# schematic-breadboard.net
KiCad netlist of a schematic drawn in EAGLE
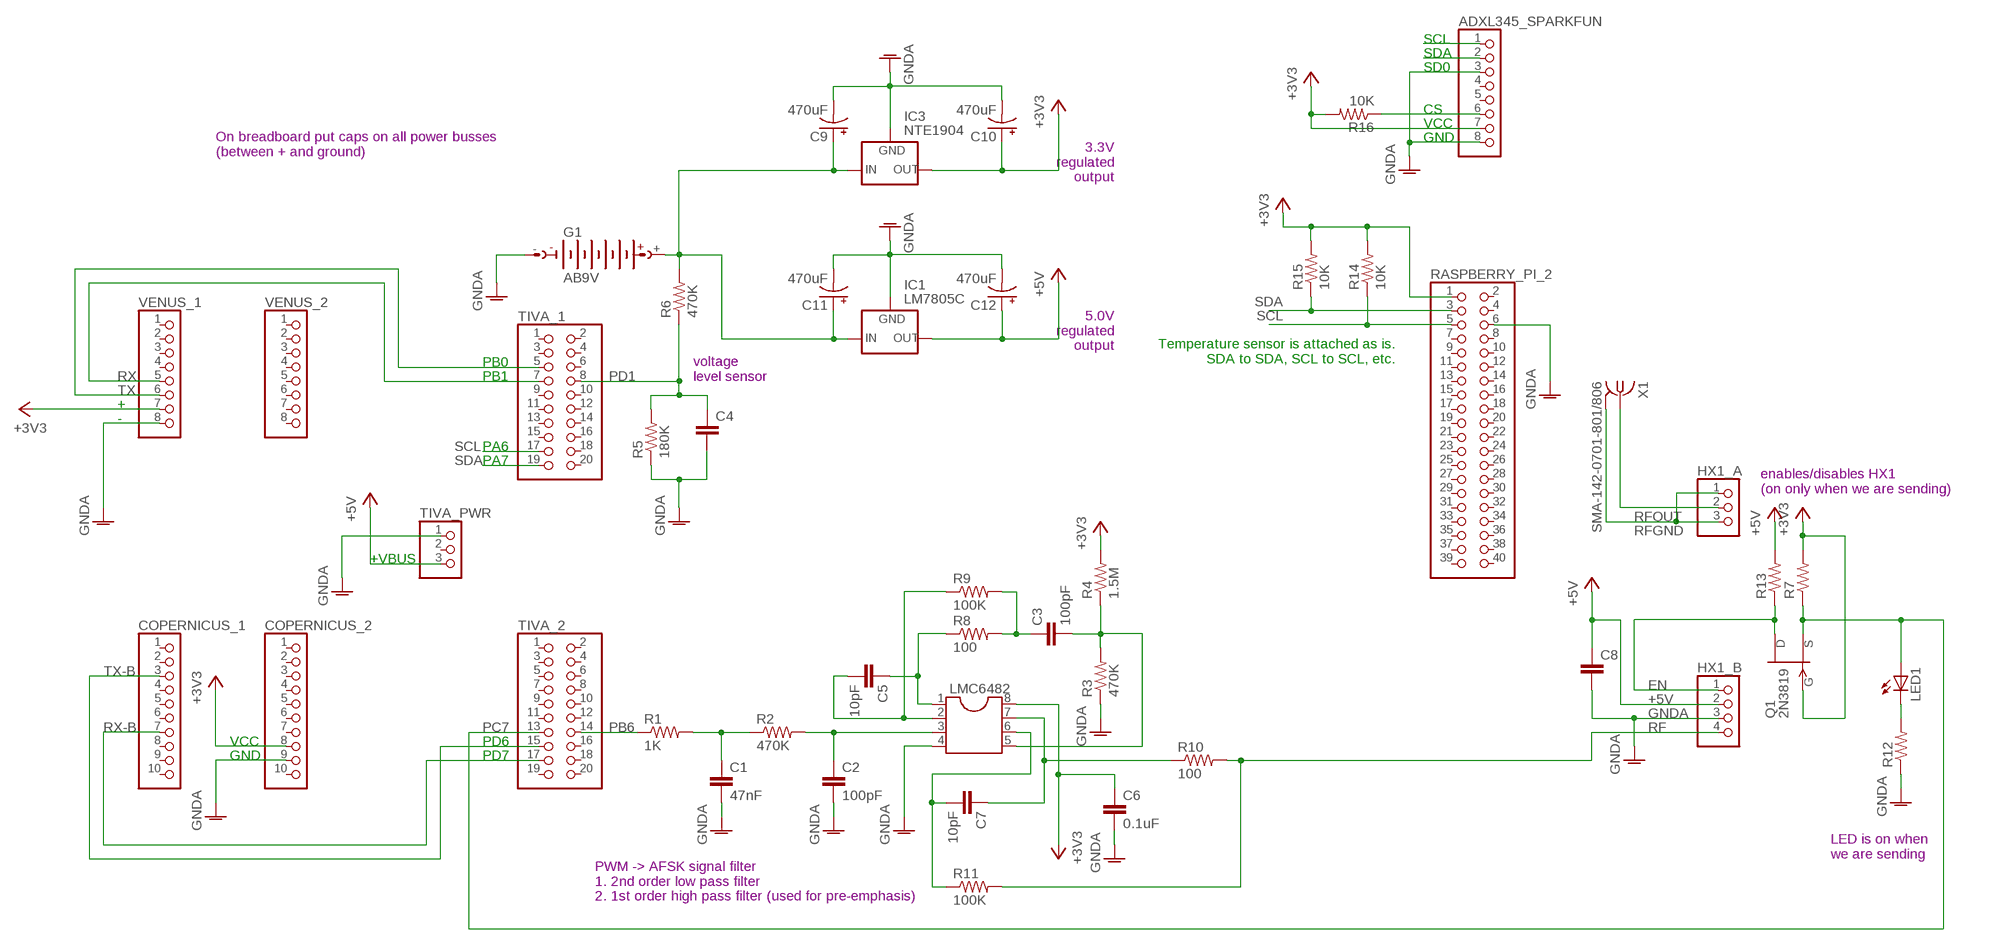
[diagram p0: schematic, sheet 1]

(export (version "E")
  (design (tool "Eeschema 10.0.6"))
  (components
    (comp (ref "ADXL345_SPARKFUN")
      (value "PINHD-1X8")
      (footprint "eagle-import:1X08")
      (libsource (lib "eagle-import") (part "PINHD-1X8"))
    )
    (comp (ref "C1")
      (value "47nF")
      (footprint "eagle-import:C2.5-2")
      (libsource (lib "eagle-import") (part "C2.5/2"))
    )
    (comp (ref "C2")
      (value "100pF")
      (footprint "eagle-import:C2.5-2")
      (libsource (lib "eagle-import") (part "C2.5/2"))
    )
    (comp (ref "C3")
      (value "100pF")
      (footprint "eagle-import:C2.5-2")
      (libsource (lib "eagle-import") (part "C2.5/2"))
    )
    (comp (ref "C4")
      (value "C2.5/2")
      (footprint "eagle-import:C2.5-2")
      (libsource (lib "eagle-import") (part "C2.5/2"))
    )
    (comp (ref "C5")
      (value "10pF")
      (footprint "eagle-import:C2.5-2")
      (libsource (lib "eagle-import") (part "C2.5/2"))
    )
    (comp (ref "C6")
      (value "0.1uF")
      (footprint "eagle-import:C2.5-2")
      (libsource (lib "eagle-import") (part "C2.5/2"))
    )
    (comp (ref "C7")
      (value "10pF")
      (footprint "eagle-import:C2.5-2")
      (libsource (lib "eagle-import") (part "C2.5/2"))
    )
    (comp (ref "C8")
      (value "C2.5/2")
      (footprint "eagle-import:C2.5-2")
      (libsource (lib "eagle-import") (part "C2.5/2"))
    )
    (comp (ref "C9")
      (value "470uF")
      (footprint "eagle-import:E2,5-6E")
      (libsource (lib "eagle-import") (part "CPOL-USE2,5-6E"))
    )
    (comp (ref "C10")
      (value "470uF")
      (footprint "eagle-import:E2,5-6E")
      (libsource (lib "eagle-import") (part "CPOL-USE2,5-6E"))
    )
    (comp (ref "C11")
      (value "470uF")
      (footprint "eagle-import:E2,5-6E")
      (libsource (lib "eagle-import") (part "CPOL-USE2,5-6E"))
    )
    (comp (ref "C12")
      (value "470uF")
      (footprint "eagle-import:E2,5-6E")
      (libsource (lib "eagle-import") (part "CPOL-USE2,5-6E"))
    )
    (comp (ref "COPERNICUS_1")
      (value "PINHD-1X10")
      (footprint "eagle-import:1X10")
      (libsource (lib "eagle-import") (part "PINHD-1X10"))
    )
    (comp (ref "COPERNICUS_2")
      (value "PINHD-1X10")
      (footprint "eagle-import:1X10")
      (libsource (lib "eagle-import") (part "PINHD-1X10"))
    )
    (comp (ref "G1")
      (value "AB9V")
      (footprint "eagle-import:AB9V")
      (libsource (lib "eagle-import") (part "AB9V"))
    )
    (comp (ref "HX1_A")
      (value "PINHD-1X3")
      (footprint "eagle-import:1X03")
      (libsource (lib "eagle-import") (part "PINHD-1X3"))
    )
    (comp (ref "HX1_B")
      (value "PINHD-1X4")
      (footprint "eagle-import:1X04")
      (libsource (lib "eagle-import") (part "PINHD-1X4"))
    )
    (comp (ref "IC1")
      (value "LM7805C")
      (footprint "eagle-import:79XXL")
      (libsource (lib "eagle-import") (part "79XXL"))
    )
    (comp (ref "IC3")
      (value "NTE1904")
      (footprint "eagle-import:79XXL")
      (libsource (lib "eagle-import") (part "79XXL"))
    )
    (comp (ref "LED1")
      (value "LED3MM")
      (footprint "eagle-import:LED3MM")
      (libsource (lib "eagle-import") (part "LED3MM"))
    )
    (comp (ref "LMC6482")
      (value "DIL8")
      (footprint "eagle-import:DIL08")
      (libsource (lib "eagle-import") (part "DIL8"))
    )
    (comp (ref "Q1")
      (value "2N3819")
      (footprint "eagle-import:TO92")
      (libsource (lib "eagle-import") (part "2N3819"))
    )
    (comp (ref "R1")
      (value "1K")
      (footprint "eagle-import:0204V")
      (libsource (lib "eagle-import") (part "R-US_0204/2V"))
    )
    (comp (ref "R2")
      (value "470K")
      (footprint "eagle-import:0204V")
      (libsource (lib "eagle-import") (part "R-US_0204/2V"))
    )
    (comp (ref "R3")
      (value "470K")
      (footprint "eagle-import:0204V")
      (libsource (lib "eagle-import") (part "R-US_0204/2V"))
    )
    (comp (ref "R4")
      (value "1.5M")
      (footprint "eagle-import:0204V")
      (libsource (lib "eagle-import") (part "R-US_0204/2V"))
    )
    (comp (ref "R5")
      (value "180K")
      (footprint "eagle-import:0204V")
      (libsource (lib "eagle-import") (part "R-US_0204/2V"))
    )
    (comp (ref "R6")
      (value "470K")
      (footprint "eagle-import:0204V")
      (libsource (lib "eagle-import") (part "R-US_0204/2V"))
    )
    (comp (ref "R7")
      (value "R-US_0204/2V")
      (footprint "eagle-import:0204V")
      (libsource (lib "eagle-import") (part "R-US_0204/2V"))
    )
    (comp (ref "R8")
      (value "100")
      (footprint "eagle-import:0204V")
      (libsource (lib "eagle-import") (part "R-US_0204/2V"))
    )
    (comp (ref "R9")
      (value "100K")
      (footprint "eagle-import:0204V")
      (libsource (lib "eagle-import") (part "R-US_0204/2V"))
    )
    (comp (ref "R10")
      (value "100")
      (footprint "eagle-import:0204V")
      (libsource (lib "eagle-import") (part "R-US_0204/2V"))
    )
    (comp (ref "R11")
      (value "100K")
      (footprint "eagle-import:0204V")
      (libsource (lib "eagle-import") (part "R-US_0204/2V"))
    )
    (comp (ref "R12")
      (value "R-US_0204/2V")
      (footprint "eagle-import:0204V")
      (libsource (lib "eagle-import") (part "R-US_0204/2V"))
    )
    (comp (ref "R13")
      (value "R-US_0204/2V")
      (footprint "eagle-import:0204V")
      (libsource (lib "eagle-import") (part "R-US_0204/2V"))
    )
    (comp (ref "R14")
      (value "10K")
      (footprint "eagle-import:0204V")
      (libsource (lib "eagle-import") (part "R-US_0204/2V"))
    )
    (comp (ref "R15")
      (value "10K")
      (footprint "eagle-import:0204V")
      (libsource (lib "eagle-import") (part "R-US_0204/2V"))
    )
    (comp (ref "R16")
      (value "10K")
      (footprint "eagle-import:0204V")
      (libsource (lib "eagle-import") (part "R-US_0204/2V"))
    )
    (comp (ref "RASPBERRY_PI_2")
      (value "PINHD-2X20")
      (footprint "eagle-import:2X20")
      (libsource (lib "eagle-import") (part "PINHD-2X20"))
    )
    (comp (ref "TIVA_1")
      (value "PINHD-2X10")
      (footprint "eagle-import:2X10")
      (libsource (lib "eagle-import") (part "PINHD-2X10"))
    )
    (comp (ref "TIVA_2")
      (value "PINHD-2X10")
      (footprint "eagle-import:2X10")
      (libsource (lib "eagle-import") (part "PINHD-2X10"))
    )
    (comp (ref "TIVA_PWR")
      (value "PINHD-1X3")
      (footprint "eagle-import:1X03")
      (libsource (lib "eagle-import") (part "PINHD-1X3"))
    )
    (comp (ref "VENUS_1")
      (value "PINHD-1X8")
      (footprint "eagle-import:1X08")
      (libsource (lib "eagle-import") (part "PINHD-1X8"))
    )
    (comp (ref "VENUS_2")
      (value "PINHD-1X8")
      (footprint "eagle-import:1X08")
      (libsource (lib "eagle-import") (part "PINHD-1X8"))
    )
    (comp (ref "X1")
      (value "SMA-142-0701-801/806")
      (footprint "eagle-import:J502-ND-142-0701-801_806")
      (fields (field (name "MF") "JOHNSON COMPONENTS") (field (name "MPN") "142-0701-801"))
      (libsource (lib "eagle-import") (part "SMA-142-0701-801/806"))
    )
  )
  (nets
    (net (code "1") (name "+3V3") (class "Default")
      (node (ref "ADXL345_SPARKFUN") (pin "7") (pinfunction "7_7") (pintype "passive"))
      (node (ref "C10") (pin "+") (pinfunction "+_+") (pintype "passive"))
      (node (ref "C6") (pin "1") (pinfunction "1_1") (pintype "passive"))
      (node (ref "COPERNICUS_2") (pin "8") (pinfunction "8_8") (pintype "passive"))
      (node (ref "IC3") (pin "OUT") (pinfunction "OUT_OUT") (pintype "passive"))
      (node (ref "LMC6482") (pin "8") (pinfunction "8_8") (pintype "passive"))
      (node (ref "Q1") (pin "2") (pinfunction "G_2") (pintype "passive"))
      (node (ref "R14") (pin "2") (pinfunction "2_2") (pintype "passive"))
      (node (ref "R15") (pin "2") (pinfunction "2_2") (pintype "passive"))
      (node (ref "R16") (pin "2") (pinfunction "2_2") (pintype "passive"))
      (node (ref "R4") (pin "2") (pinfunction "2_2") (pintype "passive"))
      (node (ref "R7") (pin "2") (pinfunction "2_2") (pintype "passive"))
      (node (ref "RASPBERRY_PI_2") (pin "1") (pinfunction "1_1") (pintype "passive"))
      (node (ref "VENUS_1") (pin "7") (pinfunction "7_7") (pintype "passive"))
    )
    (net (code "2") (name "+5V") (class "Default")
      (node (ref "C12") (pin "+") (pinfunction "+_+") (pintype "passive"))
      (node (ref "C8") (pin "1") (pinfunction "1_1") (pintype "passive"))
      (node (ref "HX1_B") (pin "2") (pinfunction "2_2") (pintype "passive"))
      (node (ref "IC1") (pin "OUT") (pinfunction "OUT_OUT") (pintype "passive"))
      (node (ref "R13") (pin "2") (pinfunction "2_2") (pintype "passive"))
      (node (ref "TIVA_PWR") (pin "3") (pinfunction "3_3") (pintype "passive"))
    )
    (net (code "3") (name "/EN") (class "Default")
      (node (ref "HX1_B") (pin "1") (pinfunction "1_1") (pintype "passive"))
      (node (ref "Q1") (pin "1") (pinfunction "D_1") (pintype "passive"))
      (node (ref "R13") (pin "1") (pinfunction "1_1") (pintype "passive"))
    )
    (net (code "4") (name "/PB6") (class "Default")
      (node (ref "R1") (pin "1") (pinfunction "1_1") (pintype "passive"))
      (node (ref "TIVA_2") (pin "14") (pinfunction "14_14") (pintype "passive"))
    )
    (net (code "5") (name "/PC7") (class "Default")
      (node (ref "LED1") (pin "A") (pinfunction "A_A") (pintype "passive"))
      (node (ref "Q1") (pin "3") (pinfunction "S_3") (pintype "passive"))
      (node (ref "R7") (pin "1") (pinfunction "1_1") (pintype "passive"))
      (node (ref "TIVA_2") (pin "13") (pinfunction "13_13") (pintype "passive"))
    )
    (net (code "6") (name "/PD1") (class "Default")
      (node (ref "C4") (pin "1") (pinfunction "1_1") (pintype "passive"))
      (node (ref "R5") (pin "2") (pinfunction "2_2") (pintype "passive"))
      (node (ref "R6") (pin "1") (pinfunction "1_1") (pintype "passive"))
      (node (ref "TIVA_1") (pin "8") (pinfunction "8_8") (pintype "passive"))
    )
    (net (code "7") (name "/RF") (class "Default")
      (node (ref "HX1_B") (pin "4") (pinfunction "4_4") (pintype "passive"))
      (node (ref "R10") (pin "2") (pinfunction "2_2") (pintype "passive"))
      (node (ref "R11") (pin "2") (pinfunction "2_2") (pintype "passive"))
    )
    (net (code "8") (name "/RFGND") (class "Default")
      (node (ref "HX1_A") (pin "1") (pinfunction "1_1") (pintype "passive"))
      (node (ref "HX1_A") (pin "3") (pinfunction "3_3") (pintype "passive"))
      (node (ref "X1") (pin "G@1") (pinfunction "2_G@1") (pintype "passive"))
      (node (ref "X1") (pin "G@2") (pinfunction "2_G@2") (pintype "passive"))
      (node (ref "X1") (pin "G@3") (pinfunction "2_G@3") (pintype "passive"))
      (node (ref "X1") (pin "G@4") (pinfunction "2_G@4") (pintype "passive"))
    )
    (net (code "9") (name "/RFOUT") (class "Default")
      (node (ref "HX1_A") (pin "2") (pinfunction "2_2") (pintype "passive"))
      (node (ref "X1") (pin "1") (pinfunction "1_1") (pintype "passive"))
    )
    (net (code "10") (name "/RX") (class "Default")
      (node (ref "TIVA_1") (pin "7") (pinfunction "7_7") (pintype "passive"))
      (node (ref "VENUS_1") (pin "5") (pinfunction "5_5") (pintype "passive"))
    )
    (net (code "11") (name "/RX-B") (class "Default")
      (node (ref "COPERNICUS_1") (pin "7") (pinfunction "7_7") (pintype "passive"))
      (node (ref "TIVA_2") (pin "17") (pinfunction "17_17") (pintype "passive"))
    )
    (net (code "12") (name "/SCL") (class "Default")
      (node (ref "R14") (pin "1") (pinfunction "1_1") (pintype "passive"))
      (node (ref "RASPBERRY_PI_2") (pin "5") (pinfunction "5_5") (pintype "passive"))
      (node (ref "TIVA_1") (pin "17") (pinfunction "17_17") (pintype "passive"))
    )
    (net (code "13") (name "/SDA") (class "Default")
      (node (ref "ADXL345_SPARKFUN") (pin "2") (pinfunction "2_2") (pintype "passive"))
      (node (ref "R15") (pin "1") (pinfunction "1_1") (pintype "passive"))
      (node (ref "RASPBERRY_PI_2") (pin "3") (pinfunction "3_3") (pintype "passive"))
      (node (ref "TIVA_1") (pin "19") (pinfunction "19_19") (pintype "passive"))
    )
    (net (code "14") (name "/TX") (class "Default")
      (node (ref "TIVA_1") (pin "5") (pinfunction "5_5") (pintype "passive"))
      (node (ref "VENUS_1") (pin "6") (pinfunction "6_6") (pintype "passive"))
    )
    (net (code "15") (name "/TX-B") (class "Default")
      (node (ref "COPERNICUS_1") (pin "3") (pinfunction "3_3") (pintype "passive"))
      (node (ref "TIVA_2") (pin "15") (pinfunction "15_15") (pintype "passive"))
    )
    (net (code "16") (name "GNDA") (class "Default")
      (node (ref "ADXL345_SPARKFUN") (pin "3") (pinfunction "3_3") (pintype "passive"))
      (node (ref "ADXL345_SPARKFUN") (pin "8") (pinfunction "8_8") (pintype "passive"))
      (node (ref "C1") (pin "2") (pinfunction "2_2") (pintype "passive"))
      (node (ref "C10") (pin "-") (pinfunction "-_-") (pintype "passive"))
      (node (ref "C11") (pin "-") (pinfunction "-_-") (pintype "passive"))
      (node (ref "C12") (pin "-") (pinfunction "-_-") (pintype "passive"))
      (node (ref "C2") (pin "2") (pinfunction "2_2") (pintype "passive"))
      (node (ref "C4") (pin "2") (pinfunction "2_2") (pintype "passive"))
      (node (ref "C6") (pin "2") (pinfunction "2_2") (pintype "passive"))
      (node (ref "C8") (pin "2") (pinfunction "2_2") (pintype "passive"))
      (node (ref "C9") (pin "-") (pinfunction "-_-") (pintype "passive"))
      (node (ref "COPERNICUS_2") (pin "9") (pinfunction "9_9") (pintype "passive"))
      (node (ref "G1") (pin "-") (pinfunction "-_-") (pintype "passive"))
      (node (ref "HX1_B") (pin "3") (pinfunction "3_3") (pintype "passive"))
      (node (ref "IC1") (pin "GND") (pinfunction "GND_GND") (pintype "input"))
      (node (ref "IC3") (pin "GND") (pinfunction "GND_GND") (pintype "input"))
      (node (ref "LMC6482") (pin "4") (pinfunction "4_4") (pintype "passive"))
      (node (ref "R12") (pin "1") (pinfunction "1_1") (pintype "passive"))
      (node (ref "R3") (pin "1") (pinfunction "1_1") (pintype "passive"))
      (node (ref "R5") (pin "1") (pinfunction "1_1") (pintype "passive"))
      (node (ref "RASPBERRY_PI_2") (pin "6") (pinfunction "6_6") (pintype "passive"))
      (node (ref "TIVA_PWR") (pin "1") (pinfunction "1_1") (pintype "passive"))
      (node (ref "VENUS_1") (pin "8") (pinfunction "8_8") (pintype "passive"))
    )
    (net (code "17") (name "Net-(ADXL345_SPARKFUN-Pad6)") (class "Default")
      (node (ref "ADXL345_SPARKFUN") (pin "6") (pinfunction "6_6") (pintype "passive"))
      (node (ref "R16") (pin "1") (pinfunction "1_1") (pintype "passive"))
    )
    (net (code "18") (name "Net-(C1-Pad1)") (class "Default")
      (node (ref "C1") (pin "1") (pinfunction "1_1") (pintype "passive"))
      (node (ref "R1") (pin "2") (pinfunction "2_2") (pintype "passive"))
      (node (ref "R2") (pin "1") (pinfunction "1_1") (pintype "passive"))
    )
    (net (code "19") (name "Net-(C2-Pad1)") (class "Default")
      (node (ref "C2") (pin "1") (pinfunction "1_1") (pintype "passive"))
      (node (ref "LMC6482") (pin "3") (pinfunction "3_3") (pintype "passive"))
      (node (ref "R2") (pin "2") (pinfunction "2_2") (pintype "passive"))
    )
    (net (code "20") (name "Net-(C3-Pad1)") (class "Default")
      (node (ref "C3") (pin "1") (pinfunction "1_1") (pintype "passive"))
      (node (ref "R8") (pin "2") (pinfunction "2_2") (pintype "passive"))
      (node (ref "R9") (pin "2") (pinfunction "2_2") (pintype "passive"))
    )
    (net (code "21") (name "Net-(C3-Pad2)") (class "Default")
      (node (ref "C3") (pin "2") (pinfunction "2_2") (pintype "passive"))
      (node (ref "LMC6482") (pin "5") (pinfunction "5_5") (pintype "passive"))
      (node (ref "R3") (pin "2") (pinfunction "2_2") (pintype "passive"))
      (node (ref "R4") (pin "1") (pinfunction "1_1") (pintype "passive"))
    )
    (net (code "22") (name "Net-(C5-Pad1)") (class "Default")
      (node (ref "C5") (pin "1") (pinfunction "1_1") (pintype "passive"))
      (node (ref "LMC6482") (pin "1") (pinfunction "1_1") (pintype "passive"))
      (node (ref "R8") (pin "1") (pinfunction "1_1") (pintype "passive"))
    )
    (net (code "23") (name "Net-(C5-Pad2)") (class "Default")
      (node (ref "C5") (pin "2") (pinfunction "2_2") (pintype "passive"))
      (node (ref "LMC6482") (pin "2") (pinfunction "2_2") (pintype "passive"))
      (node (ref "R9") (pin "1") (pinfunction "1_1") (pintype "passive"))
    )
    (net (code "24") (name "Net-(C7-Pad1)") (class "Default")
      (node (ref "C7") (pin "1") (pinfunction "1_1") (pintype "passive"))
      (node (ref "LMC6482") (pin "7") (pinfunction "7_7") (pintype "passive"))
      (node (ref "R10") (pin "1") (pinfunction "1_1") (pintype "passive"))
    )
    (net (code "25") (name "Net-(C7-Pad2)") (class "Default")
      (node (ref "C7") (pin "2") (pinfunction "2_2") (pintype "passive"))
      (node (ref "LMC6482") (pin "6") (pinfunction "6_6") (pintype "passive"))
      (node (ref "R11") (pin "1") (pinfunction "1_1") (pintype "passive"))
    )
    (net (code "26") (name "Net-(C11-Pad+)") (class "Default")
      (node (ref "C11") (pin "+") (pinfunction "+_+") (pintype "passive"))
      (node (ref "C9") (pin "+") (pinfunction "+_+") (pintype "passive"))
      (node (ref "G1") (pin "+") (pinfunction "+_+") (pintype "passive"))
      (node (ref "IC1") (pin "IN") (pinfunction "IN_IN") (pintype "input"))
      (node (ref "IC3") (pin "IN") (pinfunction "IN_IN") (pintype "input"))
      (node (ref "R6") (pin "2") (pinfunction "2_2") (pintype "passive"))
    )
    (net (code "27") (name "Net-(LED1-C)") (class "Default")
      (node (ref "LED1") (pin "K") (pinfunction "C_K") (pintype "passive"))
      (node (ref "R12") (pin "2") (pinfunction "2_2") (pintype "passive"))
    )
    (net (code "28") (name "unconnected-(ADXL345_SPARKFUN-Pad1)") (class "Default")
      (node (ref "ADXL345_SPARKFUN") (pin "1") (pinfunction "1_1") (pintype "passive"))
    )
    (net (code "29") (name "unconnected-(ADXL345_SPARKFUN-Pad4)") (class "Default")
      (node (ref "ADXL345_SPARKFUN") (pin "4") (pinfunction "4_4") (pintype "passive"))
    )
    (net (code "30") (name "unconnected-(ADXL345_SPARKFUN-Pad5)") (class "Default")
      (node (ref "ADXL345_SPARKFUN") (pin "5") (pinfunction "5_5") (pintype "passive"))
    )
    (net (code "31") (name "unconnected-(COPERNICUS_1-Pad1)") (class "Default")
      (node (ref "COPERNICUS_1") (pin "1") (pinfunction "1_1") (pintype "passive"))
    )
    (net (code "32") (name "unconnected-(COPERNICUS_1-Pad2)") (class "Default")
      (node (ref "COPERNICUS_1") (pin "2") (pinfunction "2_2") (pintype "passive"))
    )
    (net (code "33") (name "unconnected-(COPERNICUS_1-Pad4)") (class "Default")
      (node (ref "COPERNICUS_1") (pin "4") (pinfunction "4_4") (pintype "passive"))
    )
    (net (code "34") (name "unconnected-(COPERNICUS_1-Pad5)") (class "Default")
      (node (ref "COPERNICUS_1") (pin "5") (pinfunction "5_5") (pintype "passive"))
    )
    (net (code "35") (name "unconnected-(COPERNICUS_1-Pad6)") (class "Default")
      (node (ref "COPERNICUS_1") (pin "6") (pinfunction "6_6") (pintype "passive"))
    )
    (net (code "36") (name "unconnected-(COPERNICUS_1-Pad8)") (class "Default")
      (node (ref "COPERNICUS_1") (pin "8") (pinfunction "8_8") (pintype "passive"))
    )
    (net (code "37") (name "unconnected-(COPERNICUS_1-Pad9)") (class "Default")
      (node (ref "COPERNICUS_1") (pin "9") (pinfunction "9_9") (pintype "passive"))
    )
    (net (code "38") (name "unconnected-(COPERNICUS_1-Pad10)") (class "Default")
      (node (ref "COPERNICUS_1") (pin "10") (pinfunction "10_10") (pintype "passive"))
    )
    (net (code "39") (name "unconnected-(COPERNICUS_2-Pad1)") (class "Default")
      (node (ref "COPERNICUS_2") (pin "1") (pinfunction "1_1") (pintype "passive"))
    )
    (net (code "40") (name "unconnected-(COPERNICUS_2-Pad2)") (class "Default")
      (node (ref "COPERNICUS_2") (pin "2") (pinfunction "2_2") (pintype "passive"))
    )
    (net (code "41") (name "unconnected-(COPERNICUS_2-Pad3)") (class "Default")
      (node (ref "COPERNICUS_2") (pin "3") (pinfunction "3_3") (pintype "passive"))
    )
    (net (code "42") (name "unconnected-(COPERNICUS_2-Pad4)") (class "Default")
      (node (ref "COPERNICUS_2") (pin "4") (pinfunction "4_4") (pintype "passive"))
    )
    (net (code "43") (name "unconnected-(COPERNICUS_2-Pad5)") (class "Default")
      (node (ref "COPERNICUS_2") (pin "5") (pinfunction "5_5") (pintype "passive"))
    )
    (net (code "44") (name "unconnected-(COPERNICUS_2-Pad6)") (class "Default")
      (node (ref "COPERNICUS_2") (pin "6") (pinfunction "6_6") (pintype "passive"))
    )
    (net (code "45") (name "unconnected-(COPERNICUS_2-Pad7)") (class "Default")
      (node (ref "COPERNICUS_2") (pin "7") (pinfunction "7_7") (pintype "passive"))
    )
    (net (code "46") (name "unconnected-(COPERNICUS_2-Pad10)") (class "Default")
      (node (ref "COPERNICUS_2") (pin "10") (pinfunction "10_10") (pintype "passive"))
    )
    (net (code "47") (name "unconnected-(RASPBERRY_PI_2-Pad2)") (class "Default")
      (node (ref "RASPBERRY_PI_2") (pin "2") (pinfunction "2_2") (pintype "passive"))
    )
    (net (code "48") (name "unconnected-(RASPBERRY_PI_2-Pad4)") (class "Default")
      (node (ref "RASPBERRY_PI_2") (pin "4") (pinfunction "4_4") (pintype "passive"))
    )
    (net (code "49") (name "unconnected-(RASPBERRY_PI_2-Pad7)") (class "Default")
      (node (ref "RASPBERRY_PI_2") (pin "7") (pinfunction "7_7") (pintype "passive"))
    )
    (net (code "50") (name "unconnected-(RASPBERRY_PI_2-Pad8)") (class "Default")
      (node (ref "RASPBERRY_PI_2") (pin "8") (pinfunction "8_8") (pintype "passive"))
    )
    (net (code "51") (name "unconnected-(RASPBERRY_PI_2-Pad9)") (class "Default")
      (node (ref "RASPBERRY_PI_2") (pin "9") (pinfunction "9_9") (pintype "passive"))
    )
    (net (code "52") (name "unconnected-(RASPBERRY_PI_2-Pad10)") (class "Default")
      (node (ref "RASPBERRY_PI_2") (pin "10") (pinfunction "10_10") (pintype "passive"))
    )
    (net (code "53") (name "unconnected-(RASPBERRY_PI_2-Pad11)") (class "Default")
      (node (ref "RASPBERRY_PI_2") (pin "11") (pinfunction "11_11") (pintype "passive"))
    )
    (net (code "54") (name "unconnected-(RASPBERRY_PI_2-Pad12)") (class "Default")
      (node (ref "RASPBERRY_PI_2") (pin "12") (pinfunction "12_12") (pintype "passive"))
    )
    (net (code "55") (name "unconnected-(RASPBERRY_PI_2-Pad13)") (class "Default")
      (node (ref "RASPBERRY_PI_2") (pin "13") (pinfunction "13_13") (pintype "passive"))
    )
    (net (code "56") (name "unconnected-(RASPBERRY_PI_2-Pad14)") (class "Default")
      (node (ref "RASPBERRY_PI_2") (pin "14") (pinfunction "14_14") (pintype "passive"))
    )
    (net (code "57") (name "unconnected-(RASPBERRY_PI_2-Pad15)") (class "Default")
      (node (ref "RASPBERRY_PI_2") (pin "15") (pinfunction "15_15") (pintype "passive"))
    )
    (net (code "58") (name "unconnected-(RASPBERRY_PI_2-Pad16)") (class "Default")
      (node (ref "RASPBERRY_PI_2") (pin "16") (pinfunction "16_16") (pintype "passive"))
    )
    (net (code "59") (name "unconnected-(RASPBERRY_PI_2-Pad17)") (class "Default")
      (node (ref "RASPBERRY_PI_2") (pin "17") (pinfunction "17_17") (pintype "passive"))
    )
    (net (code "60") (name "unconnected-(RASPBERRY_PI_2-Pad18)") (class "Default")
      (node (ref "RASPBERRY_PI_2") (pin "18") (pinfunction "18_18") (pintype "passive"))
    )
    (net (code "61") (name "unconnected-(RASPBERRY_PI_2-Pad19)") (class "Default")
      (node (ref "RASPBERRY_PI_2") (pin "19") (pinfunction "19_19") (pintype "passive"))
    )
    (net (code "62") (name "unconnected-(RASPBERRY_PI_2-Pad20)") (class "Default")
      (node (ref "RASPBERRY_PI_2") (pin "20") (pinfunction "20_20") (pintype "passive"))
    )
    (net (code "63") (name "unconnected-(RASPBERRY_PI_2-Pad21)") (class "Default")
      (node (ref "RASPBERRY_PI_2") (pin "21") (pinfunction "21_21") (pintype "passive"))
    )
    (net (code "64") (name "unconnected-(RASPBERRY_PI_2-Pad22)") (class "Default")
      (node (ref "RASPBERRY_PI_2") (pin "22") (pinfunction "22_22") (pintype "passive"))
    )
    (net (code "65") (name "unconnected-(RASPBERRY_PI_2-Pad23)") (class "Default")
      (node (ref "RASPBERRY_PI_2") (pin "23") (pinfunction "23_23") (pintype "passive"))
    )
    (net (code "66") (name "unconnected-(RASPBERRY_PI_2-Pad24)") (class "Default")
      (node (ref "RASPBERRY_PI_2") (pin "24") (pinfunction "24_24") (pintype "passive"))
    )
    (net (code "67") (name "unconnected-(RASPBERRY_PI_2-Pad25)") (class "Default")
      (node (ref "RASPBERRY_PI_2") (pin "25") (pinfunction "25_25") (pintype "passive"))
    )
    (net (code "68") (name "unconnected-(RASPBERRY_PI_2-Pad26)") (class "Default")
      (node (ref "RASPBERRY_PI_2") (pin "26") (pinfunction "26_26") (pintype "passive"))
    )
    (net (code "69") (name "unconnected-(RASPBERRY_PI_2-Pad27)") (class "Default")
      (node (ref "RASPBERRY_PI_2") (pin "27") (pinfunction "27_27") (pintype "passive"))
    )
    (net (code "70") (name "unconnected-(RASPBERRY_PI_2-Pad28)") (class "Default")
      (node (ref "RASPBERRY_PI_2") (pin "28") (pinfunction "28_28") (pintype "passive"))
    )
    (net (code "71") (name "unconnected-(RASPBERRY_PI_2-Pad29)") (class "Default")
      (node (ref "RASPBERRY_PI_2") (pin "29") (pinfunction "29_29") (pintype "passive"))
    )
    (net (code "72") (name "unconnected-(RASPBERRY_PI_2-Pad30)") (class "Default")
      (node (ref "RASPBERRY_PI_2") (pin "30") (pinfunction "30_30") (pintype "passive"))
    )
    (net (code "73") (name "unconnected-(RASPBERRY_PI_2-Pad31)") (class "Default")
      (node (ref "RASPBERRY_PI_2") (pin "31") (pinfunction "31_31") (pintype "passive"))
    )
    (net (code "74") (name "unconnected-(RASPBERRY_PI_2-Pad32)") (class "Default")
      (node (ref "RASPBERRY_PI_2") (pin "32") (pinfunction "32_32") (pintype "passive"))
    )
    (net (code "75") (name "unconnected-(RASPBERRY_PI_2-Pad33)") (class "Default")
      (node (ref "RASPBERRY_PI_2") (pin "33") (pinfunction "33_33") (pintype "passive"))
    )
    (net (code "76") (name "unconnected-(RASPBERRY_PI_2-Pad34)") (class "Default")
      (node (ref "RASPBERRY_PI_2") (pin "34") (pinfunction "34_34") (pintype "passive"))
    )
    (net (code "77") (name "unconnected-(RASPBERRY_PI_2-Pad35)") (class "Default")
      (node (ref "RASPBERRY_PI_2") (pin "35") (pinfunction "35_35") (pintype "passive"))
    )
    (net (code "78") (name "unconnected-(RASPBERRY_PI_2-Pad36)") (class "Default")
      (node (ref "RASPBERRY_PI_2") (pin "36") (pinfunction "36_36") (pintype "passive"))
    )
    (net (code "79") (name "unconnected-(RASPBERRY_PI_2-Pad37)") (class "Default")
      (node (ref "RASPBERRY_PI_2") (pin "37") (pinfunction "37_37") (pintype "passive"))
    )
    (net (code "80") (name "unconnected-(RASPBERRY_PI_2-Pad38)") (class "Default")
      (node (ref "RASPBERRY_PI_2") (pin "38") (pinfunction "38_38") (pintype "passive"))
    )
    (net (code "81") (name "unconnected-(RASPBERRY_PI_2-Pad39)") (class "Default")
      (node (ref "RASPBERRY_PI_2") (pin "39") (pinfunction "39_39") (pintype "passive"))
    )
    (net (code "82") (name "unconnected-(RASPBERRY_PI_2-Pad40)") (class "Default")
      (node (ref "RASPBERRY_PI_2") (pin "40") (pinfunction "40_40") (pintype "passive"))
    )
    (net (code "83") (name "unconnected-(TIVA_1-Pad1)") (class "Default")
      (node (ref "TIVA_1") (pin "1") (pinfunction "1_1") (pintype "passive"))
    )
    (net (code "84") (name "unconnected-(TIVA_1-Pad2)") (class "Default")
      (node (ref "TIVA_1") (pin "2") (pinfunction "2_2") (pintype "passive"))
    )
    (net (code "85") (name "unconnected-(TIVA_1-Pad3)") (class "Default")
      (node (ref "TIVA_1") (pin "3") (pinfunction "3_3") (pintype "passive"))
    )
    (net (code "86") (name "unconnected-(TIVA_1-Pad4)") (class "Default")
      (node (ref "TIVA_1") (pin "4") (pinfunction "4_4") (pintype "passive"))
    )
    (net (code "87") (name "unconnected-(TIVA_1-Pad6)") (class "Default")
      (node (ref "TIVA_1") (pin "6") (pinfunction "6_6") (pintype "passive"))
    )
    (net (code "88") (name "unconnected-(TIVA_1-Pad9)") (class "Default")
      (node (ref "TIVA_1") (pin "9") (pinfunction "9_9") (pintype "passive"))
    )
    (net (code "89") (name "unconnected-(TIVA_1-Pad10)") (class "Default")
      (node (ref "TIVA_1") (pin "10") (pinfunction "10_10") (pintype "passive"))
    )
    (net (code "90") (name "unconnected-(TIVA_1-Pad11)") (class "Default")
      (node (ref "TIVA_1") (pin "11") (pinfunction "11_11") (pintype "passive"))
    )
    (net (code "91") (name "unconnected-(TIVA_1-Pad12)") (class "Default")
      (node (ref "TIVA_1") (pin "12") (pinfunction "12_12") (pintype "passive"))
    )
    (net (code "92") (name "unconnected-(TIVA_1-Pad13)") (class "Default")
      (node (ref "TIVA_1") (pin "13") (pinfunction "13_13") (pintype "passive"))
    )
    (net (code "93") (name "unconnected-(TIVA_1-Pad14)") (class "Default")
      (node (ref "TIVA_1") (pin "14") (pinfunction "14_14") (pintype "passive"))
    )
    (net (code "94") (name "unconnected-(TIVA_1-Pad15)") (class "Default")
      (node (ref "TIVA_1") (pin "15") (pinfunction "15_15") (pintype "passive"))
    )
    (net (code "95") (name "unconnected-(TIVA_1-Pad16)") (class "Default")
      (node (ref "TIVA_1") (pin "16") (pinfunction "16_16") (pintype "passive"))
    )
    (net (code "96") (name "unconnected-(TIVA_1-Pad18)") (class "Default")
      (node (ref "TIVA_1") (pin "18") (pinfunction "18_18") (pintype "passive"))
    )
    (net (code "97") (name "unconnected-(TIVA_1-Pad20)") (class "Default")
      (node (ref "TIVA_1") (pin "20") (pinfunction "20_20") (pintype "passive"))
    )
    (net (code "98") (name "unconnected-(TIVA_2-Pad1)") (class "Default")
      (node (ref "TIVA_2") (pin "1") (pinfunction "1_1") (pintype "passive"))
    )
    (net (code "99") (name "unconnected-(TIVA_2-Pad2)") (class "Default")
      (node (ref "TIVA_2") (pin "2") (pinfunction "2_2") (pintype "passive"))
    )
    (net (code "100") (name "unconnected-(TIVA_2-Pad3)") (class "Default")
      (node (ref "TIVA_2") (pin "3") (pinfunction "3_3") (pintype "passive"))
    )
    (net (code "101") (name "unconnected-(TIVA_2-Pad4)") (class "Default")
      (node (ref "TIVA_2") (pin "4") (pinfunction "4_4") (pintype "passive"))
    )
    (net (code "102") (name "unconnected-(TIVA_2-Pad5)") (class "Default")
      (node (ref "TIVA_2") (pin "5") (pinfunction "5_5") (pintype "passive"))
    )
    (net (code "103") (name "unconnected-(TIVA_2-Pad6)") (class "Default")
      (node (ref "TIVA_2") (pin "6") (pinfunction "6_6") (pintype "passive"))
    )
    (net (code "104") (name "unconnected-(TIVA_2-Pad7)") (class "Default")
      (node (ref "TIVA_2") (pin "7") (pinfunction "7_7") (pintype "passive"))
    )
    (net (code "105") (name "unconnected-(TIVA_2-Pad8)") (class "Default")
      (node (ref "TIVA_2") (pin "8") (pinfunction "8_8") (pintype "passive"))
    )
    (net (code "106") (name "unconnected-(TIVA_2-Pad9)") (class "Default")
      (node (ref "TIVA_2") (pin "9") (pinfunction "9_9") (pintype "passive"))
    )
    (net (code "107") (name "unconnected-(TIVA_2-Pad10)") (class "Default")
      (node (ref "TIVA_2") (pin "10") (pinfunction "10_10") (pintype "passive"))
    )
    (net (code "108") (name "unconnected-(TIVA_2-Pad11)") (class "Default")
      (node (ref "TIVA_2") (pin "11") (pinfunction "11_11") (pintype "passive"))
    )
    (net (code "109") (name "unconnected-(TIVA_2-Pad12)") (class "Default")
      (node (ref "TIVA_2") (pin "12") (pinfunction "12_12") (pintype "passive"))
    )
    (net (code "110") (name "unconnected-(TIVA_2-Pad16)") (class "Default")
      (node (ref "TIVA_2") (pin "16") (pinfunction "16_16") (pintype "passive"))
    )
    (net (code "111") (name "unconnected-(TIVA_2-Pad18)") (class "Default")
      (node (ref "TIVA_2") (pin "18") (pinfunction "18_18") (pintype "passive"))
    )
    (net (code "112") (name "unconnected-(TIVA_2-Pad19)") (class "Default")
      (node (ref "TIVA_2") (pin "19") (pinfunction "19_19") (pintype "passive"))
    )
    (net (code "113") (name "unconnected-(TIVA_2-Pad20)") (class "Default")
      (node (ref "TIVA_2") (pin "20") (pinfunction "20_20") (pintype "passive"))
    )
    (net (code "114") (name "unconnected-(TIVA_PWR-Pad2)") (class "Default")
      (node (ref "TIVA_PWR") (pin "2") (pinfunction "2_2") (pintype "passive"))
    )
    (net (code "115") (name "unconnected-(VENUS_1-Pad1)") (class "Default")
      (node (ref "VENUS_1") (pin "1") (pinfunction "1_1") (pintype "passive"))
    )
    (net (code "116") (name "unconnected-(VENUS_1-Pad2)") (class "Default")
      (node (ref "VENUS_1") (pin "2") (pinfunction "2_2") (pintype "passive"))
    )
    (net (code "117") (name "unconnected-(VENUS_1-Pad3)") (class "Default")
      (node (ref "VENUS_1") (pin "3") (pinfunction "3_3") (pintype "passive"))
    )
    (net (code "118") (name "unconnected-(VENUS_1-Pad4)") (class "Default")
      (node (ref "VENUS_1") (pin "4") (pinfunction "4_4") (pintype "passive"))
    )
    (net (code "119") (name "unconnected-(VENUS_2-Pad1)") (class "Default")
      (node (ref "VENUS_2") (pin "1") (pinfunction "1_1") (pintype "passive"))
    )
    (net (code "120") (name "unconnected-(VENUS_2-Pad2)") (class "Default")
      (node (ref "VENUS_2") (pin "2") (pinfunction "2_2") (pintype "passive"))
    )
    (net (code "121") (name "unconnected-(VENUS_2-Pad3)") (class "Default")
      (node (ref "VENUS_2") (pin "3") (pinfunction "3_3") (pintype "passive"))
    )
    (net (code "122") (name "unconnected-(VENUS_2-Pad4)") (class "Default")
      (node (ref "VENUS_2") (pin "4") (pinfunction "4_4") (pintype "passive"))
    )
    (net (code "123") (name "unconnected-(VENUS_2-Pad5)") (class "Default")
      (node (ref "VENUS_2") (pin "5") (pinfunction "5_5") (pintype "passive"))
    )
    (net (code "124") (name "unconnected-(VENUS_2-Pad6)") (class "Default")
      (node (ref "VENUS_2") (pin "6") (pinfunction "6_6") (pintype "passive"))
    )
    (net (code "125") (name "unconnected-(VENUS_2-Pad7)") (class "Default")
      (node (ref "VENUS_2") (pin "7") (pinfunction "7_7") (pintype "passive"))
    )
    (net (code "126") (name "unconnected-(VENUS_2-Pad8)") (class "Default")
      (node (ref "VENUS_2") (pin "8") (pinfunction "8_8") (pintype "passive"))
    )
  )
)
